# CD74HC4067_MUX_1.net
KiCad netlist of a schematic drawn in Altium Designer
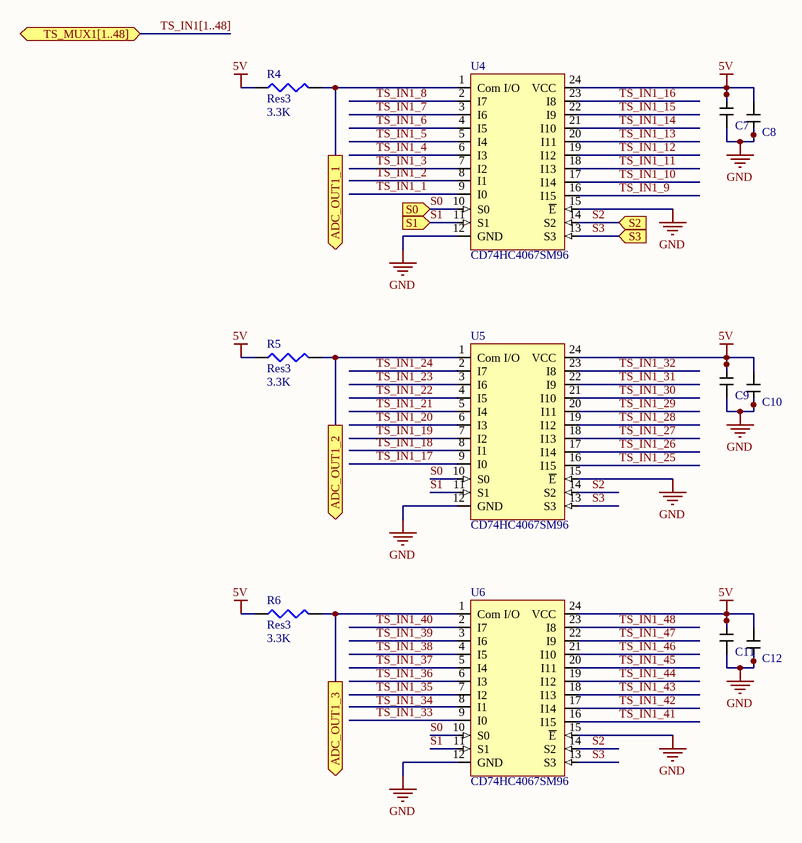
[diagram p0: CD74HC4067_MUX_1.SchDoc]

(export (version "E")
  (design (tool "Eeschema 10.0.6"))
  (components
    (comp (ref "C7")
      (value "0.1uF Cap")
      (footprint "CAPC1608X09M")
      (description "C0603C101K8GAC7867 Kemet Capacitor")
      (libsource (lib "0.1_uF_Kemet_Cap") (part "0.1uF Cap"))
    )
    (comp (ref "C8")
      (value "1uF Samsung Cap")
      (footprint "CAPC1608X09M")
      (libsource (lib "1uF_Samsung_Cap") (part "1uF Samsung Cap"))
    )
    (comp (ref "C9")
      (value "0.1uF Cap")
      (footprint "CAPC1608X09M")
      (description "C0603C101K8GAC7867 Kemet Capacitor")
      (libsource (lib "0.1_uF_Kemet_Cap") (part "0.1uF Cap"))
    )
    (comp (ref "C10")
      (value "1uF Samsung Cap")
      (footprint "CAPC1608X09M")
      (libsource (lib "1uF_Samsung_Cap") (part "1uF Samsung Cap"))
    )
    (comp (ref "C11")
      (value "0.1uF Cap")
      (footprint "CAPC1608X09M")
      (description "C0603C101K8GAC7867 Kemet Capacitor")
      (libsource (lib "0.1_uF_Kemet_Cap") (part "0.1uF Cap"))
    )
    (comp (ref "C12")
      (value "1uF Samsung Cap")
      (footprint "CAPC1608X09M")
      (libsource (lib "1uF_Samsung_Cap") (part "1uF Samsung Cap"))
    )
    (comp (ref "R4")
      (value "Res3")
      (footprint "J1-0603")
      (description "Resistor")
      (fields (field (name "ALTIUM_VALUE") "3.3K") (field (name "PUBLISHER") "Altium Limited"))
      (libsource (lib "Miscellaneous Devices") (part "Res3"))
    )
    (comp (ref "R5")
      (value "Res3")
      (footprint "J1-0603")
      (description "Resistor")
      (fields (field (name "ALTIUM_VALUE") "3.3K") (field (name "PUBLISHER") "Altium Limited"))
      (libsource (lib "Miscellaneous Devices") (part "Res3"))
    )
    (comp (ref "R6")
      (value "Res3")
      (footprint "J1-0603")
      (description "Resistor")
      (fields (field (name "ALTIUM_VALUE") "3.3K") (field (name "PUBLISHER") "Altium Limited"))
      (libsource (lib "Miscellaneous Devices") (part "Res3"))
    )
    (comp (ref "U4")
      (value "CD74HC4067SM96")
      (footprint "SOIC-24_MUX")
      (libsource (lib "TI_Mux") (part "CD74HC4067SM96"))
    )
    (comp (ref "U5")
      (value "CD74HC4067SM96")
      (footprint "SOIC-24_MUX")
      (libsource (lib "TI_Mux") (part "CD74HC4067SM96"))
    )
    (comp (ref "U6")
      (value "CD74HC4067SM96")
      (footprint "SOIC-24_MUX")
      (libsource (lib "TI_Mux") (part "CD74HC4067SM96"))
    )
  )
  (nets
    (net (code "49") (name "/ADC_OUT1_1") (class "Default")
      (node (ref "R4") (pin "2") (pinfunction "2_2") (pintype "passive"))
      (node (ref "U4") (pin "1") (pinfunction "Com_I/O_1") (pintype "bidirectional"))
    )
    (net (code "50") (name "/ADC_OUT1_2") (class "Default")
      (node (ref "R5") (pin "2") (pinfunction "2_2") (pintype "passive"))
      (node (ref "U5") (pin "1") (pinfunction "Com_I/O_1") (pintype "bidirectional"))
    )
    (net (code "51") (name "/ADC_OUT1_3") (class "Default")
      (node (ref "R6") (pin "2") (pinfunction "2_2") (pintype "passive"))
      (node (ref "U6") (pin "1") (pinfunction "Com_I/O_1") (pintype "bidirectional"))
    )
    (net (code "52") (name "/S0") (class "Default")
      (node (ref "U4") (pin "10") (pinfunction "S0_10") (pintype "input"))
      (node (ref "U5") (pin "10") (pinfunction "S0_10") (pintype "input"))
      (node (ref "U6") (pin "10") (pinfunction "S0_10") (pintype "input"))
    )
    (net (code "53") (name "/S1") (class "Default")
      (node (ref "U4") (pin "11") (pinfunction "S1_11") (pintype "input"))
      (node (ref "U5") (pin "11") (pinfunction "S1_11") (pintype "input"))
      (node (ref "U6") (pin "11") (pinfunction "S1_11") (pintype "input"))
    )
    (net (code "54") (name "/S2") (class "Default")
      (node (ref "U4") (pin "14") (pinfunction "S2_14") (pintype "input"))
      (node (ref "U5") (pin "14") (pinfunction "S2_14") (pintype "input"))
      (node (ref "U6") (pin "14") (pinfunction "S2_14") (pintype "input"))
    )
    (net (code "55") (name "/S3") (class "Default")
      (node (ref "U4") (pin "13") (pinfunction "S3_13") (pintype "input"))
      (node (ref "U5") (pin "13") (pinfunction "S3_13") (pintype "input"))
      (node (ref "U6") (pin "13") (pinfunction "S3_13") (pintype "input"))
    )
    (net (code "57") (name "/TS_IN1_1") (class "Default")
      (node (ref "U4") (pin "9") (pinfunction "I0_9") (pintype "passive"))
    )
    (net (code "58") (name "/TS_IN1_2") (class "Default")
      (node (ref "U4") (pin "8") (pinfunction "I1_8") (pintype "passive"))
    )
    (net (code "59") (name "/TS_IN1_3") (class "Default")
      (node (ref "U4") (pin "7") (pinfunction "I2_7") (pintype "passive"))
    )
    (net (code "60") (name "/TS_IN1_4") (class "Default")
      (node (ref "U4") (pin "6") (pinfunction "I3_6") (pintype "passive"))
    )
    (net (code "61") (name "/TS_IN1_5") (class "Default")
      (node (ref "U4") (pin "5") (pinfunction "I4_5") (pintype "passive"))
    )
    (net (code "62") (name "/TS_IN1_6") (class "Default")
      (node (ref "U4") (pin "4") (pinfunction "I5_4") (pintype "passive"))
    )
    (net (code "63") (name "/TS_IN1_7") (class "Default")
      (node (ref "U4") (pin "3") (pinfunction "I6_3") (pintype "passive"))
    )
    (net (code "64") (name "/TS_IN1_8") (class "Default")
      (node (ref "U4") (pin "2") (pinfunction "I7_2") (pintype "passive"))
    )
    (net (code "65") (name "/TS_IN1_9") (class "Default")
      (node (ref "U4") (pin "16") (pinfunction "I15_16") (pintype "passive"))
    )
    (net (code "66") (name "/TS_IN1_10") (class "Default")
      (node (ref "U4") (pin "17") (pinfunction "I14_17") (pintype "passive"))
    )
    (net (code "67") (name "/TS_IN1_11") (class "Default")
      (node (ref "U4") (pin "18") (pinfunction "I13_18") (pintype "passive"))
    )
    (net (code "68") (name "/TS_IN1_12") (class "Default")
      (node (ref "U4") (pin "19") (pinfunction "I12_19") (pintype "passive"))
    )
    (net (code "69") (name "/TS_IN1_13") (class "Default")
      (node (ref "U4") (pin "20") (pinfunction "I11_20") (pintype "passive"))
    )
    (net (code "70") (name "/TS_IN1_14") (class "Default")
      (node (ref "U4") (pin "21") (pinfunction "I10_21") (pintype "passive"))
    )
    (net (code "71") (name "/TS_IN1_15") (class "Default")
      (node (ref "U4") (pin "22") (pinfunction "I9_22") (pintype "passive"))
    )
    (net (code "72") (name "/TS_IN1_16") (class "Default")
      (node (ref "U4") (pin "23") (pinfunction "I8_23") (pintype "passive"))
    )
    (net (code "73") (name "/TS_IN1_17") (class "Default")
      (node (ref "U5") (pin "9") (pinfunction "I0_9") (pintype "passive"))
    )
    (net (code "74") (name "/TS_IN1_18") (class "Default")
      (node (ref "U5") (pin "8") (pinfunction "I1_8") (pintype "passive"))
    )
    (net (code "75") (name "/TS_IN1_19") (class "Default")
      (node (ref "U5") (pin "7") (pinfunction "I2_7") (pintype "passive"))
    )
    (net (code "76") (name "/TS_IN1_20") (class "Default")
      (node (ref "U5") (pin "6") (pinfunction "I3_6") (pintype "passive"))
    )
    (net (code "77") (name "/TS_IN1_21") (class "Default")
      (node (ref "U5") (pin "5") (pinfunction "I4_5") (pintype "passive"))
    )
    (net (code "78") (name "/TS_IN1_22") (class "Default")
      (node (ref "U5") (pin "4") (pinfunction "I5_4") (pintype "passive"))
    )
    (net (code "79") (name "/TS_IN1_23") (class "Default")
      (node (ref "U5") (pin "3") (pinfunction "I6_3") (pintype "passive"))
    )
    (net (code "80") (name "/TS_IN1_24") (class "Default")
      (node (ref "U5") (pin "2") (pinfunction "I7_2") (pintype "passive"))
    )
    (net (code "81") (name "/TS_IN1_25") (class "Default")
      (node (ref "U5") (pin "16") (pinfunction "I15_16") (pintype "passive"))
    )
    (net (code "82") (name "/TS_IN1_26") (class "Default")
      (node (ref "U5") (pin "17") (pinfunction "I14_17") (pintype "passive"))
    )
    (net (code "83") (name "/TS_IN1_27") (class "Default")
      (node (ref "U5") (pin "18") (pinfunction "I13_18") (pintype "passive"))
    )
    (net (code "84") (name "/TS_IN1_28") (class "Default")
      (node (ref "U5") (pin "19") (pinfunction "I12_19") (pintype "passive"))
    )
    (net (code "85") (name "/TS_IN1_29") (class "Default")
      (node (ref "U5") (pin "20") (pinfunction "I11_20") (pintype "passive"))
    )
    (net (code "86") (name "/TS_IN1_30") (class "Default")
      (node (ref "U5") (pin "21") (pinfunction "I10_21") (pintype "passive"))
    )
    (net (code "87") (name "/TS_IN1_31") (class "Default")
      (node (ref "U5") (pin "22") (pinfunction "I9_22") (pintype "passive"))
    )
    (net (code "88") (name "/TS_IN1_32") (class "Default")
      (node (ref "U5") (pin "23") (pinfunction "I8_23") (pintype "passive"))
    )
    (net (code "89") (name "/TS_IN1_33") (class "Default")
      (node (ref "U6") (pin "9") (pinfunction "I0_9") (pintype "passive"))
    )
    (net (code "91") (name "/TS_IN1_35") (class "Default")
      (node (ref "U6") (pin "7") (pinfunction "I2_7") (pintype "passive"))
    )
    (net (code "92") (name "/TS_IN1_36") (class "Default")
      (node (ref "U6") (pin "6") (pinfunction "I3_6") (pintype "passive"))
    )
    (net (code "93") (name "/TS_IN1_37") (class "Default")
      (node (ref "U6") (pin "5") (pinfunction "I4_5") (pintype "passive"))
    )
    (net (code "94") (name "/TS_IN1_38") (class "Default")
      (node (ref "U6") (pin "4") (pinfunction "I5_4") (pintype "passive"))
    )
    (net (code "95") (name "/TS_IN1_39") (class "Default")
      (node (ref "U6") (pin "3") (pinfunction "I6_3") (pintype "passive"))
    )
    (net (code "96") (name "/TS_IN1_40") (class "Default")
      (node (ref "U6") (pin "2") (pinfunction "I7_2") (pintype "passive"))
    )
    (net (code "97") (name "/TS_IN1_41") (class "Default")
      (node (ref "U6") (pin "16") (pinfunction "I15_16") (pintype "passive"))
    )
    (net (code "98") (name "/TS_IN1_42") (class "Default")
      (node (ref "U6") (pin "17") (pinfunction "I14_17") (pintype "passive"))
    )
    (net (code "99") (name "/TS_IN1_43") (class "Default")
      (node (ref "U6") (pin "18") (pinfunction "I13_18") (pintype "passive"))
    )
    (net (code "100") (name "/TS_IN1_44") (class "Default")
      (node (ref "U6") (pin "19") (pinfunction "I12_19") (pintype "passive"))
    )
    (net (code "101") (name "/TS_IN1_45") (class "Default")
      (node (ref "U6") (pin "20") (pinfunction "I11_20") (pintype "passive"))
    )
    (net (code "102") (name "/TS_IN1_46") (class "Default")
      (node (ref "U6") (pin "21") (pinfunction "I10_21") (pintype "passive"))
    )
    (net (code "103") (name "/TS_IN1_47") (class "Default")
      (node (ref "U6") (pin "22") (pinfunction "I9_22") (pintype "passive"))
    )
    (net (code "104") (name "/TS_IN1_48") (class "Default")
      (node (ref "U6") (pin "23") (pinfunction "I8_23") (pintype "passive"))
    )
    (net (code "105") (name "5V") (class "Default")
      (node (ref "C10") (pin "2") (pinfunction "2_2") (pintype "passive"))
      (node (ref "C11") (pin "2") (pinfunction "2_2") (pintype "passive"))
      (node (ref "C12") (pin "2") (pinfunction "2_2") (pintype "passive"))
      (node (ref "C7") (pin "2") (pinfunction "2_2") (pintype "passive"))
      (node (ref "C8") (pin "2") (pinfunction "2_2") (pintype "passive"))
      (node (ref "C9") (pin "2") (pinfunction "2_2") (pintype "passive"))
      (node (ref "R4") (pin "1") (pinfunction "1_1") (pintype "passive"))
      (node (ref "R5") (pin "1") (pinfunction "1_1") (pintype "passive"))
      (node (ref "R6") (pin "1") (pinfunction "1_1") (pintype "passive"))
      (node (ref "U4") (pin "24") (pinfunction "VCC_24") (pintype "power_in"))
      (node (ref "U5") (pin "24") (pinfunction "VCC_24") (pintype "power_in"))
      (node (ref "U6") (pin "24") (pinfunction "VCC_24") (pintype "power_in"))
    )
    (net (code "106") (name "GND") (class "Default")
      (node (ref "C10") (pin "1") (pinfunction "1_1") (pintype "passive"))
      (node (ref "C11") (pin "1") (pinfunction "1_1") (pintype "passive"))
      (node (ref "C12") (pin "1") (pinfunction "1_1") (pintype "passive"))
      (node (ref "C7") (pin "1") (pinfunction "1_1") (pintype "passive"))
      (node (ref "C8") (pin "1") (pinfunction "1_1") (pintype "passive"))
      (node (ref "C9") (pin "1") (pinfunction "1_1") (pintype "passive"))
      (node (ref "U4") (pin "12") (pinfunction "GND_12") (pintype "power_in"))
      (node (ref "U4") (pin "15") (pinfunction "~{E}_15") (pintype "input"))
      (node (ref "U5") (pin "12") (pinfunction "GND_12") (pintype "power_in"))
      (node (ref "U5") (pin "15") (pinfunction "~{E}_15") (pintype "input"))
      (node (ref "U6") (pin "12") (pinfunction "GND_12") (pintype "power_in"))
      (node (ref "U6") (pin "15") (pinfunction "~{E}_15") (pintype "input"))
    )
    (net (code "107") (name "unconnected-(U6-I1-Pad8)") (class "Default")
      (node (ref "U6") (pin "8") (pinfunction "I1_8") (pintype "passive"))
    )
  )
)
